# Sheet3.net
KiCad netlist of a schematic drawn in Altium Designer
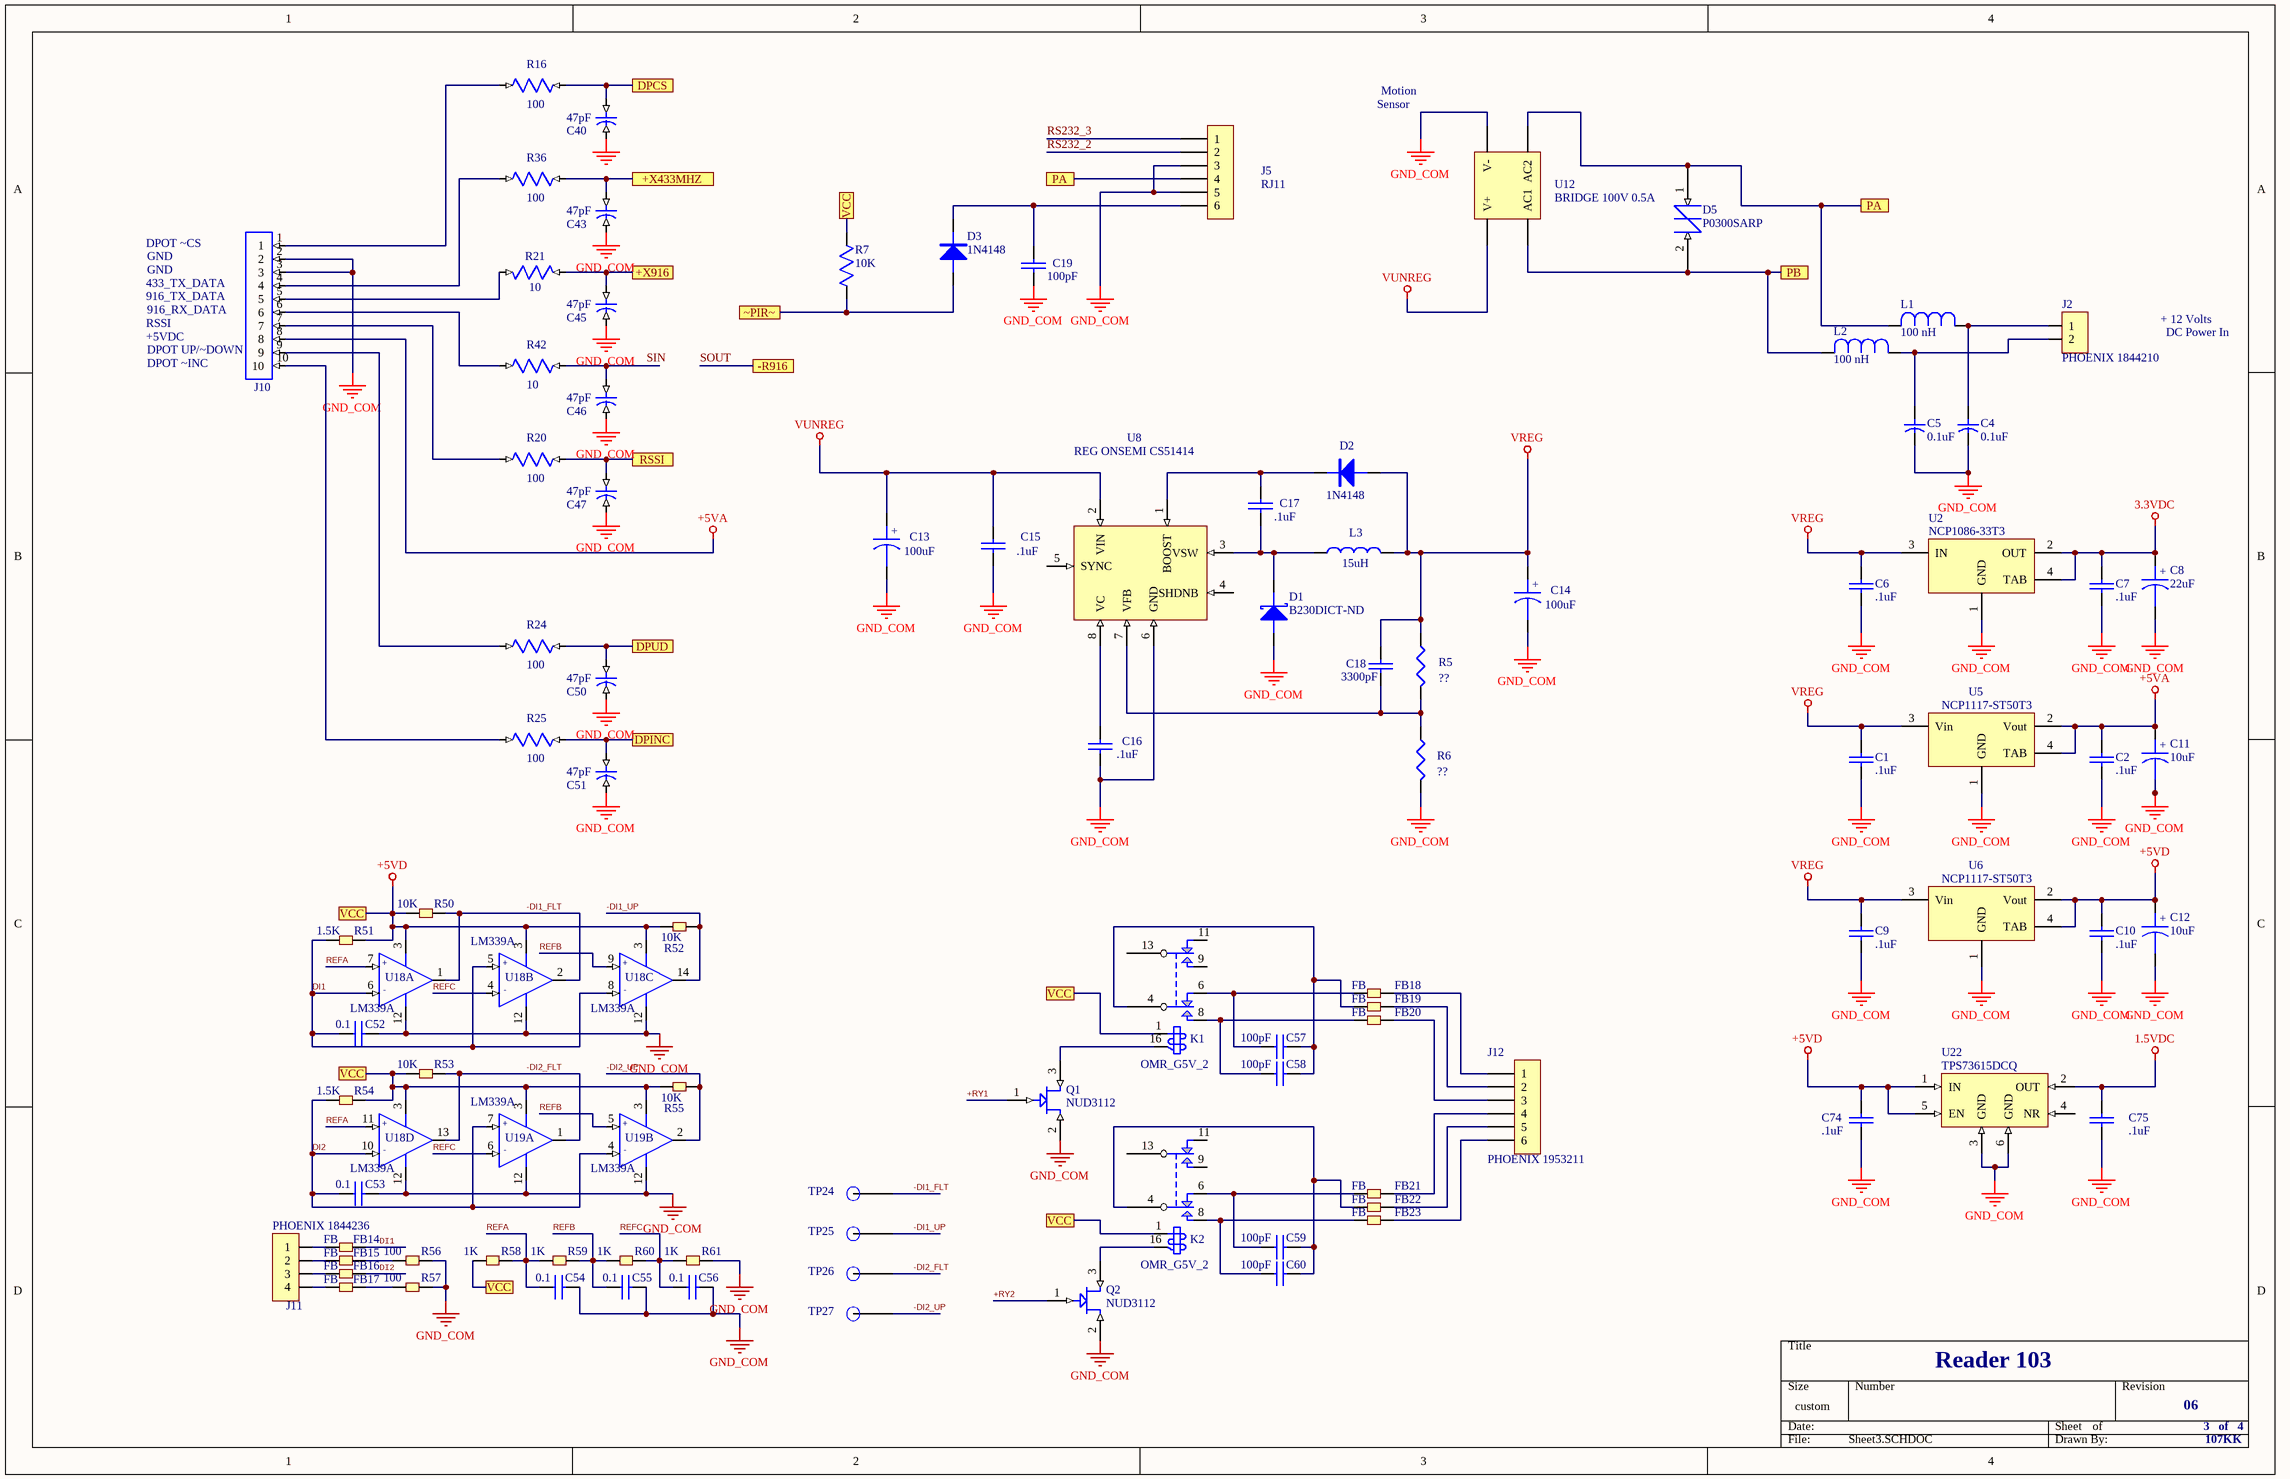
[diagram p0: Sheet3.SCHDOC]

(export (version "E")
  (design (tool "Eeschema 10.0.6"))
  (components
    (comp (ref "C1")
      (value ".1uF")
      (footprint "0603")
      (description "Capacitor")
      (libsource (lib "*") (part "CAP"))
    )
    (comp (ref "C2")
      (value ".1uF")
      (footprint "0603")
      (description "Capacitor")
      (libsource (lib "*") (part "CAP"))
    )
    (comp (ref "C4") (value "0.1uF") (footprint "0603") (libsource (lib "*") (part "C_0603")))
    (comp (ref "C5") (value "0.1uF") (footprint "0603") (libsource (lib "*") (part "C_0603")))
    (comp (ref "C6")
      (value ".1uF")
      (footprint "0603")
      (description "Capacitor")
      (libsource (lib "*") (part "CAP"))
    )
    (comp (ref "C7")
      (value ".1uF")
      (footprint "0603")
      (description "Capacitor")
      (libsource (lib "*") (part "CAP"))
    )
    (comp (ref "C8")
      (value "22uF")
      (footprint "CAP A CASE")
      (description "Capacitor")
      (libsource (lib "*") (part "CAPACITOR POL"))
    )
    (comp (ref "C9")
      (value ".1uF")
      (footprint "0603")
      (description "Capacitor")
      (libsource (lib "*") (part "CAP"))
    )
    (comp (ref "C10")
      (value ".1uF")
      (footprint "0603")
      (description "Capacitor")
      (libsource (lib "*") (part "CAP"))
    )
    (comp (ref "C11")
      (value "10uF")
      (footprint "CAP A CASE")
      (description "Capacitor")
      (libsource (lib "*") (part "CAPACITOR POL"))
    )
    (comp (ref "C12")
      (value "10uF")
      (footprint "CAP A CASE")
      (description "Capacitor")
      (libsource (lib "*") (part "CAPACITOR POL"))
    )
    (comp (ref "C13")
      (value "100uF")
      (footprint "CAP D CASE")
      (description "Capacitor")
      (libsource (lib "*") (part "CAPACITOR POL"))
    )
    (comp (ref "C14")
      (value "100uF")
      (footprint "CAP D CASE")
      (description "Capacitor")
      (libsource (lib "*") (part "CAPACITOR POL"))
    )
    (comp (ref "C15")
      (value ".1uF")
      (footprint "0603")
      (description "Capacitor")
      (libsource (lib "*") (part "CAP"))
    )
    (comp (ref "C16")
      (value ".1uF")
      (footprint "0603")
      (description "Capacitor")
      (libsource (lib "*") (part "CAP"))
    )
    (comp (ref "C17")
      (value ".1uF")
      (footprint "0603")
      (description "Capacitor")
      (libsource (lib "*") (part "CAP"))
    )
    (comp (ref "C18")
      (value "3300pF")
      (footprint "0603")
      (description "Capacitor")
      (libsource (lib "*") (part "CAP"))
    )
    (comp (ref "C19")
      (value "100pF")
      (footprint "0603")
      (description "Capacitor")
      (libsource (lib "*") (part "CAP"))
    )
    (comp (ref "C40") (value "47pF") (footprint "0603") (libsource (lib "*") (part "C0603")))
    (comp (ref "C43") (value "47pF") (footprint "0603") (libsource (lib "*") (part "C0603")))
    (comp (ref "C45") (value "47pF") (footprint "0603") (libsource (lib "*") (part "C0603")))
    (comp (ref "C46") (value "47pF") (footprint "0603") (libsource (lib "*") (part "C0603")))
    (comp (ref "C47") (value "47pF") (footprint "0603") (libsource (lib "*") (part "C0603")))
    (comp (ref "C50") (value "47pF") (footprint "0603") (libsource (lib "*") (part "C0603")))
    (comp (ref "C51") (value "47pF") (footprint "0603") (libsource (lib "*") (part "C0603")))
    (comp (ref "C52") (value "0.1") (footprint "0603") (libsource (lib "*") (part "CAP NP_1")))
    (comp (ref "C53") (value "0.1") (footprint "0603") (libsource (lib "*") (part "CAP NP_1")))
    (comp (ref "C54") (value "0.1") (footprint "0603") (libsource (lib "*") (part "CAP NP_1")))
    (comp (ref "C55") (value "0.1") (footprint "0603") (libsource (lib "*") (part "CAP NP_1")))
    (comp (ref "C56") (value "0.1") (footprint "0603") (libsource (lib "*") (part "CAP NP_1")))
    (comp (ref "C57") (value "100pF") (footprint "0603") (libsource (lib "*") (part "CAP NP_1")))
    (comp (ref "C58") (value "100pF") (footprint "0603") (libsource (lib "*") (part "CAP NP_1")))
    (comp (ref "C59") (value "100pF") (footprint "0603") (libsource (lib "*") (part "CAP NP_1")))
    (comp (ref "C60") (value "100pF") (footprint "0603") (libsource (lib "*") (part "CAP NP_1")))
    (comp (ref "C74")
      (value ".1uF")
      (footprint "0603")
      (description "Capacitor")
      (libsource (lib "*") (part "CAP"))
    )
    (comp (ref "C75")
      (value ".1uF")
      (footprint "0603")
      (description "Capacitor")
      (libsource (lib "*") (part "CAP"))
    )
    (comp (ref "D1")
      (value "B230DICT-ND")
      (footprint "DIODE SMB")
      (description "Schottky Diode")
      (libsource (lib "*") (part "DIODE SCHOTTKY"))
    )
    (comp (ref "D2")
      (value "1N4148")
      (footprint "SOD123")
      (description "Diode")
      (libsource (lib "*") (part "DIODE"))
    )
    (comp (ref "D3")
      (value "1N4148")
      (footprint "SOD123")
      (description "Diode")
      (libsource (lib "*") (part "DIODE"))
    )
    (comp (ref "D5") (value "P0300SARP") (footprint "TRANSORB_1") (libsource (lib "*") (part "TRANSORB")))
    (comp (ref "FB14") (value "FB") (footprint "0603") (libsource (lib "*") (part "FB")))
    (comp (ref "FB15") (value "FB") (footprint "0603") (libsource (lib "*") (part "FB")))
    (comp (ref "FB16") (value "FB") (footprint "0603") (libsource (lib "*") (part "FB")))
    (comp (ref "FB17") (value "FB") (footprint "0603") (libsource (lib "*") (part "FB")))
    (comp (ref "FB18") (value "FB") (footprint "0603") (libsource (lib "*") (part "FB")))
    (comp (ref "FB19") (value "FB") (footprint "0603") (libsource (lib "*") (part "FB")))
    (comp (ref "FB20") (value "FB") (footprint "0603") (libsource (lib "*") (part "FB")))
    (comp (ref "FB21") (value "FB") (footprint "0603") (libsource (lib "*") (part "FB")))
    (comp (ref "FB22") (value "FB") (footprint "0603") (libsource (lib "*") (part "FB")))
    (comp (ref "FB23") (value "FB") (footprint "0603") (libsource (lib "*") (part "FB")))
    (comp (ref "J2")
      (value "PHOENIX 1844210")
      (footprint "CONN PHOENIX 1844210-2")
      (description "Connector")
      (libsource (lib "*") (part "CON2"))
    )
    (comp (ref "J5")
      (value "RJ11")
      (footprint "RJ11")
      (description "Connector")
      (libsource (lib "*") (part "CON6"))
    )
    (comp (ref "J10") (value "1X10 HEADER") (footprint "HDR_10") (libsource (lib "*") (part "HDR10")))
    (comp (ref "J11")
      (value "PHOENIX 1844236")
      (footprint "CONN PHOENIX 1844236-4")
      (libsource (lib "*") (part "CON4"))
    )
    (comp (ref "J12")
      (value "PHOENIX 1953211")
      (footprint "CONN PHOENIX 1953211-6")
      (description "Connector")
      (libsource (lib "*") (part "CON6"))
    )
    (comp (ref "K1") (value "OMR_G5V_2") (footprint "RELAY44") (libsource (lib "*") (part "OMRON_G5V_3")))
    (comp (ref "K2") (value "OMR_G5V_2") (footprint "RELAY44") (libsource (lib "*") (part "OMRON_G5V_3")))
    (comp (ref "L1") (value "100 nH") (footprint "0603") (libsource (lib "*") (part "INDUCTOR_1")))
    (comp (ref "L2") (value "100 nH") (footprint "0603") (libsource (lib "*") (part "INDUCTOR_1")))
    (comp (ref "L3")
      (value "15uH")
      (footprint "COIL COILTRONICS UP2B-150")
      (libsource (lib "*") (part "INDUCTOR1"))
    )
    (comp (ref "Q1")
      (value "NUD3112")
      (footprint "SOT23")
      (libsource (lib "*") (part "INDUCTIVE LOAD DRIVER"))
    )
    (comp (ref "Q2")
      (value "NUD3112")
      (footprint "SOT23")
      (libsource (lib "*") (part "INDUCTIVE LOAD DRIVER"))
    )
    (comp (ref "R5") (value "??") (footprint "0603") (libsource (lib "*") (part "RES1")))
    (comp (ref "R6") (value "??") (footprint "0603") (libsource (lib "*") (part "RES1")))
    (comp (ref "R7") (value "10K") (footprint "0603") (libsource (lib "*") (part "R_0603")))
    (comp (ref "R16") (value "100") (footprint "0603") (libsource (lib "*") (part "R0603")))
    (comp (ref "R20") (value "100") (footprint "0603") (libsource (lib "*") (part "R0603")))
    (comp (ref "R21") (value "10") (footprint "0603") (libsource (lib "*") (part "R_603")))
    (comp (ref "R24") (value "100") (footprint "0603") (libsource (lib "*") (part "R0603")))
    (comp (ref "R25") (value "100") (footprint "0603") (libsource (lib "*") (part "R0603")))
    (comp (ref "R36") (value "100") (footprint "0603") (libsource (lib "*") (part "R0603")))
    (comp (ref "R42") (value "10") (footprint "0603") (libsource (lib "*") (part "R0603")))
    (comp (ref "R50") (value "10K") (footprint "0603") (libsource (lib "*") (part "RS")))
    (comp (ref "R51") (value "1.5K") (footprint "0603") (libsource (lib "*") (part "RS")))
    (comp (ref "R52") (value "10K") (footprint "0603") (libsource (lib "*") (part "RS")))
    (comp (ref "R53") (value "10K") (footprint "0603") (libsource (lib "*") (part "RS")))
    (comp (ref "R54") (value "1.5K") (footprint "0603") (libsource (lib "*") (part "RS")))
    (comp (ref "R55") (value "10K") (footprint "0603") (libsource (lib "*") (part "RS")))
    (comp (ref "R56") (value "100") (footprint "0603") (libsource (lib "*") (part "RS")))
    (comp (ref "R57") (value "100") (footprint "0603") (libsource (lib "*") (part "RS")))
    (comp (ref "R58") (value "1K") (footprint "0603") (libsource (lib "*") (part "RS")))
    (comp (ref "R59") (value "1K") (footprint "0603") (libsource (lib "*") (part "RS")))
    (comp (ref "R60") (value "1K") (footprint "0603") (libsource (lib "*") (part "RS")))
    (comp (ref "R61") (value "1K") (footprint "0603") (libsource (lib "*") (part "RS")))
    (comp (ref "TP24") (value "TP") (footprint "TEST POINT PAD 3") (libsource (lib "*") (part "TESTPOINT_1")))
    (comp (ref "TP25") (value "TP") (footprint "TEST POINT PAD 3") (libsource (lib "*") (part "TESTPOINT_1")))
    (comp (ref "TP26") (value "TP") (footprint "TEST POINT PAD 3") (libsource (lib "*") (part "TESTPOINT_1")))
    (comp (ref "TP27") (value "TP") (footprint "TEST POINT PAD 3") (libsource (lib "*") (part "TESTPOINT_1")))
    (comp (ref "U2")
      (value "NCP1086-33T3")
      (footprint "SOT223 REG")
      (libsource (lib "Reader-Rev6") (part "REG GOI"))
    )
    (comp (ref "U5")
      (value "NCP1117-ST50T3")
      (footprint "SOT223 REG")
      (libsource (lib "Reader-Rev6") (part "REG REVERSED"))
    )
    (comp (ref "U6")
      (value "NCP1117-ST50T3")
      (footprint "SOT223 REG")
      (libsource (lib "Reader-Rev6") (part "REG REVERSED"))
    )
    (comp (ref "U8")
      (value "REG ONSEMI CS51414")
      (footprint "SO8")
      (libsource (lib "*") (part "REG ONSEMI CS51414"))
    )
    (comp (ref "U12")
      (value "BRIDGE 100V 0.5A")
      (footprint "BRIDGE")
      (description "Diode Bridge")
      (libsource (lib "*") (part "BRIDGE2"))
    )
    (comp (ref "U18") (value "LM339A") (footprint "SO14") (libsource (lib "*") (part "LM339")))
    (comp (ref "U19") (value "LM339A") (footprint "SO14") (libsource (lib "*") (part "LM339")))
    (comp (ref "U22")
      (value "TPS73615DCQ")
      (footprint "SOT223-5")
      (libsource (lib "*") (part "REG SOT223-5"))
    )
  )
  (nets
    (net (code "1") (name "+5VA") (class "Default")
      (node (ref "C11") (pin "1") (pinfunction "1_1") (pintype "passive"))
      (node (ref "C2") (pin "1") (pinfunction "1_1") (pintype "passive"))
      (node (ref "J10") (pin "8") (pinfunction "8_8") (pintype "input"))
      (node (ref "U5") (pin "2") (pinfunction "Vout_2") (pintype "passive"))
      (node (ref "U5") (pin "4") (pinfunction "TAB_4") (pintype "passive"))
    )
    (net (code "2") (name "+5VD") (class "Default")
      (node (ref "C10") (pin "1") (pinfunction "1_1") (pintype "passive"))
      (node (ref "C12") (pin "1") (pinfunction "1_1") (pintype "passive"))
      (node (ref "C74") (pin "1") (pinfunction "1_1") (pintype "passive"))
      (node (ref "K1") (pin "1") (pinfunction "COIL1_1") (pintype "passive"))
      (node (ref "K2") (pin "1") (pinfunction "COIL1_1") (pintype "passive"))
      (node (ref "R50") (pin "2") (pinfunction "2_2") (pintype "passive"))
      (node (ref "R51") (pin "1") (pinfunction "1_1") (pintype "passive"))
      (node (ref "R52") (pin "2") (pinfunction "2_2") (pintype "passive"))
      (node (ref "R53") (pin "2") (pinfunction "2_2") (pintype "passive"))
      (node (ref "R54") (pin "1") (pinfunction "1_1") (pintype "passive"))
      (node (ref "R55") (pin "2") (pinfunction "2_2") (pintype "passive"))
      (node (ref "R58") (pin "2") (pinfunction "2_2") (pintype "passive"))
      (node (ref "R7") (pin "1") (pinfunction "A_1") (pintype "passive"))
      (node (ref "U18") (pin "3") (pinfunction "V+_3") (pintype "power_in"))
      (node (ref "U19") (pin "3") (pinfunction "V+_3") (pintype "power_in"))
      (node (ref "U22") (pin "1") (pinfunction "IN_1") (pintype "input"))
      (node (ref "U22") (pin "5") (pinfunction "EN_5") (pintype "input"))
      (node (ref "U6") (pin "2") (pinfunction "Vout_2") (pintype "passive"))
      (node (ref "U6") (pin "4") (pinfunction "TAB_4") (pintype "passive"))
    )
    (net (code "3") (name "/+RY1") (class "Default")
      (node (ref "Q1") (pin "1") (pinfunction "G_1") (pintype "input"))
    )
    (net (code "4") (name "/+RY2") (class "Default")
      (node (ref "Q2") (pin "1") (pinfunction "G_1") (pintype "input"))
    )
    (net (code "5") (name "/+X433MHZ") (class "Default")
      (node (ref "C43") (pin "1") (pinfunction "A_1") (pintype "input"))
      (node (ref "R36") (pin "2") (pinfunction "B_2") (pintype "input"))
    )
    (net (code "6") (name "/+X916") (class "Default")
      (node (ref "C45") (pin "1") (pinfunction "A_1") (pintype "input"))
      (node (ref "R21") (pin "1") (pinfunction "A_1") (pintype "input"))
    )
    (net (code "7") (name "/-DI1_FLT") (class "Default")
      (node (ref "R50") (pin "1") (pinfunction "1_1") (pintype "passive"))
      (node (ref "TP24") (pin "1") (pinfunction "TP_1") (pintype "passive"))
      (node (ref "U18") (pin "1") (pinfunction "OUT_1") (pintype "open_collector"))
      (node (ref "U18") (pin "2") (pinfunction "OUT_2") (pintype "open_collector"))
    )
    (net (code "8") (name "/-DI1_UP") (class "Default")
      (node (ref "R52") (pin "1") (pinfunction "1_1") (pintype "passive"))
      (node (ref "TP25") (pin "1") (pinfunction "TP_1") (pintype "passive"))
      (node (ref "U18") (pin "14") (pinfunction "OUT_14") (pintype "open_collector"))
    )
    (net (code "9") (name "/-DI2_FLT") (class "Default")
      (node (ref "R53") (pin "1") (pinfunction "1_1") (pintype "passive"))
      (node (ref "TP26") (pin "1") (pinfunction "TP_1") (pintype "passive"))
      (node (ref "U18") (pin "13") (pinfunction "OUT_13") (pintype "open_collector"))
      (node (ref "U19") (pin "1") (pinfunction "OUT_1") (pintype "open_collector"))
    )
    (net (code "10") (name "/-DI2_UP") (class "Default")
      (node (ref "R55") (pin "1") (pinfunction "1_1") (pintype "passive"))
      (node (ref "TP27") (pin "1") (pinfunction "TP_1") (pintype "passive"))
      (node (ref "U19") (pin "2") (pinfunction "OUT_2") (pintype "open_collector"))
    )
    (net (code "11") (name "/DI1") (class "Default")
      (node (ref "C52") (pin "1") (pinfunction "1_1") (pintype "passive"))
      (node (ref "FB14") (pin "1") (pinfunction "1_1") (pintype "passive"))
      (node (ref "R51") (pin "2") (pinfunction "2_2") (pintype "passive"))
      (node (ref "U18") (pin "5") (pinfunction "+_5") (pintype "input"))
      (node (ref "U18") (pin "6") (pinfunction "-_6") (pintype "input"))
      (node (ref "U18") (pin "8") (pinfunction "-_8") (pintype "input"))
    )
    (net (code "12") (name "/DI2") (class "Default")
      (node (ref "C53") (pin "1") (pinfunction "1_1") (pintype "passive"))
      (node (ref "FB16") (pin "1") (pinfunction "1_1") (pintype "passive"))
      (node (ref "R54") (pin "2") (pinfunction "2_2") (pintype "passive"))
      (node (ref "U18") (pin "10") (pinfunction "-_10") (pintype "input"))
      (node (ref "U19") (pin "4") (pinfunction "-_4") (pintype "input"))
      (node (ref "U19") (pin "7") (pinfunction "+_7") (pintype "input"))
    )
    (net (code "13") (name "/DPCS") (class "Default")
      (node (ref "C40") (pin "1") (pinfunction "A_1") (pintype "input"))
      (node (ref "R16") (pin "2") (pinfunction "B_2") (pintype "input"))
    )
    (net (code "14") (name "/DPINC") (class "Default")
      (node (ref "C51") (pin "1") (pinfunction "A_1") (pintype "input"))
      (node (ref "R25") (pin "2") (pinfunction "B_2") (pintype "input"))
    )
    (net (code "15") (name "/DPUD") (class "Default")
      (node (ref "C50") (pin "1") (pinfunction "A_1") (pintype "input"))
      (node (ref "R24") (pin "2") (pinfunction "B_2") (pintype "input"))
    )
    (net (code "16") (name "/PA") (class "Default")
      (node (ref "D5") (pin "1") (pinfunction "1_1") (pintype "input"))
      (node (ref "J5") (pin "4") (pinfunction "4_4") (pintype "passive"))
      (node (ref "L1") (pin "1") (pinfunction "B_1") (pintype "passive"))
      (node (ref "U12") (pin "AC2") (pinfunction "AC2_AC2") (pintype "passive"))
    )
    (net (code "17") (name "/PB") (class "Default")
      (node (ref "D5") (pin "2") (pinfunction "2_2") (pintype "input"))
      (node (ref "L2") (pin "1") (pinfunction "B_1") (pintype "passive"))
      (node (ref "U12") (pin "AC1") (pinfunction "AC1_AC1") (pintype "passive"))
    )
    (net (code "18") (name "/REFA") (class "Default")
      (node (ref "C54") (pin "1") (pinfunction "1_1") (pintype "passive"))
      (node (ref "R58") (pin "1") (pinfunction "1_1") (pintype "passive"))
      (node (ref "R59") (pin "2") (pinfunction "2_2") (pintype "passive"))
      (node (ref "U18") (pin "11") (pinfunction "+_11") (pintype "input"))
      (node (ref "U18") (pin "7") (pinfunction "+_7") (pintype "input"))
    )
    (net (code "19") (name "/REFB") (class "Default")
      (node (ref "C55") (pin "1") (pinfunction "1_1") (pintype "passive"))
      (node (ref "R59") (pin "1") (pinfunction "1_1") (pintype "passive"))
      (node (ref "R60") (pin "2") (pinfunction "2_2") (pintype "passive"))
      (node (ref "U18") (pin "9") (pinfunction "+_9") (pintype "input"))
      (node (ref "U19") (pin "5") (pinfunction "+_5") (pintype "input"))
    )
    (net (code "20") (name "/REFC") (class "Default")
      (node (ref "C56") (pin "1") (pinfunction "1_1") (pintype "passive"))
      (node (ref "R60") (pin "1") (pinfunction "1_1") (pintype "passive"))
      (node (ref "R61") (pin "2") (pinfunction "2_2") (pintype "passive"))
      (node (ref "U18") (pin "4") (pinfunction "-_4") (pintype "input"))
      (node (ref "U19") (pin "6") (pinfunction "-_6") (pintype "input"))
    )
    (net (code "21") (name "/RS232_2") (class "Default")
      (node (ref "J5") (pin "2") (pinfunction "2_2") (pintype "passive"))
    )
    (net (code "22") (name "/RS232_3") (class "Default")
      (node (ref "J5") (pin "1") (pinfunction "1_1") (pintype "passive"))
    )
    (net (code "23") (name "/RSSI") (class "Default")
      (node (ref "C47") (pin "1") (pinfunction "A_1") (pintype "input"))
      (node (ref "R20") (pin "2") (pinfunction "B_2") (pintype "input"))
    )
    (net (code "24") (name "/SIN") (class "Default")
      (node (ref "C46") (pin "1") (pinfunction "A_1") (pintype "input"))
      (node (ref "R42") (pin "2") (pinfunction "B_2") (pintype "input"))
    )
    (net (code "26") (name "/~PIR~") (class "Default")
      (node (ref "D3") (pin "A") (pinfunction "A_A") (pintype "passive"))
      (node (ref "R7") (pin "2") (pinfunction "B_2") (pintype "passive"))
    )
    (net (code "27") (name "1.5VDC") (class "Default")
      (node (ref "C75") (pin "1") (pinfunction "1_1") (pintype "passive"))
      (node (ref "U22") (pin "2") (pinfunction "OUT_2") (pintype "input"))
    )
    (net (code "28") (name "3.3VDC") (class "Default")
      (node (ref "C7") (pin "1") (pinfunction "1_1") (pintype "passive"))
      (node (ref "C8") (pin "1") (pinfunction "1_1") (pintype "passive"))
      (node (ref "U2") (pin "2") (pinfunction "OUT_2") (pintype "power_in"))
      (node (ref "U2") (pin "4") (pinfunction "TAB_4") (pintype "power_in"))
    )
    (net (code "29") (name "GND_COM") (class "Default")
      (node (ref "C1") (pin "2") (pinfunction "2_2") (pintype "passive"))
      (node (ref "C10") (pin "2") (pinfunction "2_2") (pintype "passive"))
      (node (ref "C11") (pin "2") (pinfunction "2_2") (pintype "passive"))
      (node (ref "C12") (pin "2") (pinfunction "2_2") (pintype "passive"))
      (node (ref "C13") (pin "2") (pinfunction "2_2") (pintype "passive"))
      (node (ref "C14") (pin "2") (pinfunction "2_2") (pintype "passive"))
      (node (ref "C15") (pin "2") (pinfunction "2_2") (pintype "passive"))
      (node (ref "C16") (pin "2") (pinfunction "2_2") (pintype "passive"))
      (node (ref "C19") (pin "2") (pinfunction "2_2") (pintype "passive"))
      (node (ref "C2") (pin "2") (pinfunction "2_2") (pintype "passive"))
      (node (ref "C4") (pin "2") (pinfunction "B_2") (pintype "passive"))
      (node (ref "C40") (pin "2") (pinfunction "B_2") (pintype "input"))
      (node (ref "C43") (pin "2") (pinfunction "B_2") (pintype "input"))
      (node (ref "C45") (pin "2") (pinfunction "B_2") (pintype "input"))
      (node (ref "C46") (pin "2") (pinfunction "B_2") (pintype "input"))
      (node (ref "C47") (pin "2") (pinfunction "B_2") (pintype "input"))
      (node (ref "C5") (pin "2") (pinfunction "B_2") (pintype "passive"))
      (node (ref "C50") (pin "2") (pinfunction "B_2") (pintype "input"))
      (node (ref "C51") (pin "2") (pinfunction "B_2") (pintype "input"))
      (node (ref "C52") (pin "2") (pinfunction "2_2") (pintype "passive"))
      (node (ref "C53") (pin "2") (pinfunction "2_2") (pintype "passive"))
      (node (ref "C54") (pin "2") (pinfunction "2_2") (pintype "passive"))
      (node (ref "C55") (pin "2") (pinfunction "2_2") (pintype "passive"))
      (node (ref "C56") (pin "2") (pinfunction "2_2") (pintype "passive"))
      (node (ref "C6") (pin "2") (pinfunction "2_2") (pintype "passive"))
      (node (ref "C7") (pin "2") (pinfunction "2_2") (pintype "passive"))
      (node (ref "C74") (pin "2") (pinfunction "2_2") (pintype "passive"))
      (node (ref "C75") (pin "2") (pinfunction "2_2") (pintype "passive"))
      (node (ref "C8") (pin "2") (pinfunction "2_2") (pintype "passive"))
      (node (ref "C9") (pin "2") (pinfunction "2_2") (pintype "passive"))
      (node (ref "D1") (pin "A") (pinfunction "A_A") (pintype "passive"))
      (node (ref "J10") (pin "2") (pinfunction "2_2") (pintype "input"))
      (node (ref "J10") (pin "3") (pinfunction "3_3") (pintype "input"))
      (node (ref "J5") (pin "3") (pinfunction "3_3") (pintype "passive"))
      (node (ref "J5") (pin "5") (pinfunction "5_5") (pintype "passive"))
      (node (ref "Q1") (pin "2") (pinfunction "S_2") (pintype "input"))
      (node (ref "Q2") (pin "2") (pinfunction "S_2") (pintype "input"))
      (node (ref "R56") (pin "1") (pinfunction "1_1") (pintype "passive"))
      (node (ref "R57") (pin "1") (pinfunction "1_1") (pintype "passive"))
      (node (ref "R6") (pin "2") (pinfunction "2_2") (pintype "passive"))
      (node (ref "R61") (pin "1") (pinfunction "1_1") (pintype "passive"))
      (node (ref "U12") (pin "V-") (pinfunction "V-_V-") (pintype "passive"))
      (node (ref "U18") (pin "12") (pinfunction "V-_12") (pintype "power_in"))
      (node (ref "U19") (pin "12") (pinfunction "V-_12") (pintype "power_in"))
      (node (ref "U2") (pin "1") (pinfunction "GND_1") (pintype "power_in"))
      (node (ref "U22") (pin "3") (pinfunction "GND_3") (pintype "input"))
      (node (ref "U22") (pin "6") (pinfunction "GND_6") (pintype "input"))
      (node (ref "U5") (pin "1") (pinfunction "GND_1") (pintype "passive"))
      (node (ref "U6") (pin "1") (pinfunction "GND_1") (pintype "passive"))
      (node (ref "U8") (pin "6") (pinfunction "GND_6") (pintype "input"))
    )
    (net (code "30") (name "Net-(C4-A)") (class "Default")
      (node (ref "C4") (pin "1") (pinfunction "A_1") (pintype "passive"))
      (node (ref "J2") (pin "1") (pinfunction "1_1") (pintype "passive"))
      (node (ref "L1") (pin "2") (pinfunction "A_2") (pintype "passive"))
    )
    (net (code "31") (name "Net-(C5-A)") (class "Default")
      (node (ref "C5") (pin "1") (pinfunction "A_1") (pintype "passive"))
      (node (ref "J2") (pin "2") (pinfunction "2_2") (pintype "passive"))
      (node (ref "L2") (pin "2") (pinfunction "A_2") (pintype "passive"))
    )
    (net (code "32") (name "Net-(C19-Pad1)") (class "Default")
      (node (ref "C19") (pin "1") (pinfunction "1_1") (pintype "passive"))
      (node (ref "D3") (pin "K") (pinfunction "K_K") (pintype "passive"))
      (node (ref "J5") (pin "6") (pinfunction "6_6") (pintype "passive"))
    )
    (net (code "33") (name "Net-(FB14-Pad2)") (class "Default")
      (node (ref "FB14") (pin "2") (pinfunction "2_2") (pintype "passive"))
      (node (ref "J11") (pin "1") (pinfunction "1_1") (pintype "passive"))
    )
    (net (code "34") (name "Net-(FB15-Pad1)") (class "Default")
      (node (ref "FB15") (pin "1") (pinfunction "1_1") (pintype "passive"))
      (node (ref "R56") (pin "2") (pinfunction "2_2") (pintype "passive"))
    )
    (net (code "35") (name "Net-(FB15-Pad2)") (class "Default")
      (node (ref "FB15") (pin "2") (pinfunction "2_2") (pintype "passive"))
      (node (ref "J11") (pin "2") (pinfunction "2_2") (pintype "passive"))
    )
    (net (code "36") (name "Net-(FB16-Pad2)") (class "Default")
      (node (ref "FB16") (pin "2") (pinfunction "2_2") (pintype "passive"))
      (node (ref "J11") (pin "3") (pinfunction "3_3") (pintype "passive"))
    )
    (net (code "37") (name "Net-(FB17-Pad1)") (class "Default")
      (node (ref "FB17") (pin "1") (pinfunction "1_1") (pintype "passive"))
      (node (ref "R57") (pin "2") (pinfunction "2_2") (pintype "passive"))
    )
    (net (code "38") (name "Net-(FB17-Pad2)") (class "Default")
      (node (ref "FB17") (pin "2") (pinfunction "2_2") (pintype "passive"))
      (node (ref "J11") (pin "4") (pinfunction "4_4") (pintype "passive"))
    )
    (net (code "39") (name "Net-(FB18-Pad1)") (class "Default")
      (node (ref "FB18") (pin "1") (pinfunction "1_1") (pintype "passive"))
      (node (ref "J12") (pin "1") (pinfunction "1_1") (pintype "passive"))
    )
    (net (code "40") (name "Net-(FB19-Pad1)") (class "Default")
      (node (ref "FB19") (pin "1") (pinfunction "1_1") (pintype "passive"))
      (node (ref "J12") (pin "2") (pinfunction "2_2") (pintype "passive"))
    )
    (net (code "41") (name "Net-(FB20-Pad1)") (class "Default")
      (node (ref "FB20") (pin "1") (pinfunction "1_1") (pintype "passive"))
      (node (ref "J12") (pin "3") (pinfunction "3_3") (pintype "passive"))
    )
    (net (code "42") (name "Net-(FB21-Pad1)") (class "Default")
      (node (ref "FB21") (pin "1") (pinfunction "1_1") (pintype "passive"))
      (node (ref "J12") (pin "4") (pinfunction "4_4") (pintype "passive"))
    )
    (net (code "43") (name "Net-(FB22-Pad1)") (class "Default")
      (node (ref "FB22") (pin "1") (pinfunction "1_1") (pintype "passive"))
      (node (ref "J12") (pin "5") (pinfunction "5_5") (pintype "passive"))
    )
    (net (code "44") (name "Net-(FB23-Pad1)") (class "Default")
      (node (ref "FB23") (pin "1") (pinfunction "1_1") (pintype "passive"))
      (node (ref "J12") (pin "6") (pinfunction "6_6") (pintype "passive"))
    )
    (net (code "45") (name "Net-(K1-COIL2)") (class "Default")
      (node (ref "K1") (pin "16") (pinfunction "COIL2_16") (pintype "passive"))
      (node (ref "Q1") (pin "3") (pinfunction "D_3") (pintype "input"))
    )
    (net (code "46") (name "Net-(K1-COMMON2)") (class "Default")
      (node (ref "C57") (pin "2") (pinfunction "2_2") (pintype "passive"))
      (node (ref "C58") (pin "2") (pinfunction "2_2") (pintype "passive"))
      (node (ref "FB19") (pin "2") (pinfunction "2_2") (pintype "passive"))
      (node (ref "K1") (pin "4") (pinfunction "COMMON2_4") (pintype "passive"))
    )
    (net (code "47") (name "Net-(K1-NC2)") (class "Default")
      (node (ref "C57") (pin "1") (pinfunction "1_1") (pintype "passive"))
      (node (ref "FB18") (pin "2") (pinfunction "2_2") (pintype "passive"))
      (node (ref "K1") (pin "6") (pinfunction "NC2_6") (pintype "passive"))
    )
    (net (code "48") (name "Net-(K1-NO2)") (class "Default")
      (node (ref "C58") (pin "1") (pinfunction "1_1") (pintype "passive"))
      (node (ref "FB20") (pin "2") (pinfunction "2_2") (pintype "passive"))
      (node (ref "K1") (pin "8") (pinfunction "NO2_8") (pintype "passive"))
    )
    (net (code "49") (name "Net-(K2-COIL2)") (class "Default")
      (node (ref "K2") (pin "16") (pinfunction "COIL2_16") (pintype "passive"))
      (node (ref "Q2") (pin "3") (pinfunction "D_3") (pintype "input"))
    )
    (net (code "50") (name "Net-(K2-COMMON2)") (class "Default")
      (node (ref "C59") (pin "2") (pinfunction "2_2") (pintype "passive"))
      (node (ref "C60") (pin "2") (pinfunction "2_2") (pintype "passive"))
      (node (ref "FB22") (pin "2") (pinfunction "2_2") (pintype "passive"))
      (node (ref "K2") (pin "4") (pinfunction "COMMON2_4") (pintype "passive"))
    )
    (net (code "51") (name "Net-(K2-NC2)") (class "Default")
      (node (ref "C59") (pin "1") (pinfunction "1_1") (pintype "passive"))
      (node (ref "FB21") (pin "2") (pinfunction "2_2") (pintype "passive"))
      (node (ref "K2") (pin "6") (pinfunction "NC2_6") (pintype "passive"))
    )
    (net (code "52") (name "Net-(K2-NO2)") (class "Default")
      (node (ref "C60") (pin "1") (pinfunction "1_1") (pintype "passive"))
      (node (ref "FB23") (pin "2") (pinfunction "2_2") (pintype "passive"))
      (node (ref "K2") (pin "8") (pinfunction "NO2_8") (pintype "passive"))
    )
    (net (code "53") (name "Net-(R16-A)") (class "Default")
      (node (ref "J10") (pin "1") (pinfunction "1_1") (pintype "input"))
      (node (ref "R16") (pin "1") (pinfunction "A_1") (pintype "input"))
    )
    (net (code "54") (name "Net-(R20-A)") (class "Default")
      (node (ref "J10") (pin "7") (pinfunction "7_7") (pintype "input"))
      (node (ref "R20") (pin "1") (pinfunction "A_1") (pintype "input"))
    )
    (net (code "55") (name "Net-(R21-B)") (class "Default")
      (node (ref "J10") (pin "5") (pinfunction "5_5") (pintype "input"))
      (node (ref "R21") (pin "2") (pinfunction "B_2") (pintype "input"))
    )
    (net (code "56") (name "Net-(R24-A)") (class "Default")
      (node (ref "J10") (pin "9") (pinfunction "9_9") (pintype "input"))
      (node (ref "R24") (pin "1") (pinfunction "A_1") (pintype "input"))
    )
    (net (code "57") (name "Net-(R25-A)") (class "Default")
      (node (ref "J10") (pin "10") (pinfunction "10_10") (pintype "input"))
      (node (ref "R25") (pin "1") (pinfunction "A_1") (pintype "input"))
    )
    (net (code "58") (name "Net-(R36-A)") (class "Default")
      (node (ref "J10") (pin "4") (pinfunction "4_4") (pintype "input"))
      (node (ref "R36") (pin "1") (pinfunction "A_1") (pintype "input"))
    )
    (net (code "59") (name "Net-(R42-A)") (class "Default")
      (node (ref "J10") (pin "6") (pinfunction "6_6") (pintype "input"))
      (node (ref "R42") (pin "1") (pinfunction "A_1") (pintype "input"))
    )
    (net (code "60") (name "Net-(U8-BOOST)") (class "Default")
      (node (ref "C17") (pin "1") (pinfunction "1_1") (pintype "passive"))
      (node (ref "D2") (pin "K") (pinfunction "K_K") (pintype "passive"))
      (node (ref "U8") (pin "1") (pinfunction "BOOST_1") (pintype "input"))
    )
    (net (code "61") (name "Net-(U8-VC)") (class "Default")
      (node (ref "C16") (pin "1") (pinfunction "1_1") (pintype "passive"))
      (node (ref "U8") (pin "8") (pinfunction "VC_8") (pintype "input"))
    )
    (net (code "62") (name "Net-(U8-VFB)") (class "Default")
      (node (ref "C18") (pin "2") (pinfunction "2_2") (pintype "passive"))
      (node (ref "R5") (pin "2") (pinfunction "2_2") (pintype "passive"))
      (node (ref "R6") (pin "1") (pinfunction "1_1") (pintype "passive"))
      (node (ref "U8") (pin "7") (pinfunction "VFB_7") (pintype "input"))
    )
    (net (code "63") (name "Net-(U8-VSW)") (class "Default")
      (node (ref "C17") (pin "2") (pinfunction "2_2") (pintype "passive"))
      (node (ref "D1") (pin "K") (pinfunction "K_K") (pintype "passive"))
      (node (ref "L3") (pin "1") (pinfunction "1_1") (pintype "passive"))
      (node (ref "U8") (pin "3") (pinfunction "VSW_3") (pintype "input"))
    )
    (net (code "64") (name "VREG") (class "Default")
      (node (ref "C1") (pin "1") (pinfunction "1_1") (pintype "passive"))
      (node (ref "C14") (pin "1") (pinfunction "1_1") (pintype "passive"))
      (node (ref "C18") (pin "1") (pinfunction "1_1") (pintype "passive"))
      (node (ref "C6") (pin "1") (pinfunction "1_1") (pintype "passive"))
      (node (ref "C9") (pin "1") (pinfunction "1_1") (pintype "passive"))
      (node (ref "D2") (pin "A") (pinfunction "A_A") (pintype "passive"))
      (node (ref "L3") (pin "2") (pinfunction "2_2") (pintype "passive"))
      (node (ref "R5") (pin "1") (pinfunction "1_1") (pintype "passive"))
      (node (ref "U2") (pin "3") (pinfunction "IN_3") (pintype "power_in"))
      (node (ref "U5") (pin "3") (pinfunction "Vin_3") (pintype "passive"))
      (node (ref "U6") (pin "3") (pinfunction "Vin_3") (pintype "passive"))
    )
    (net (code "65") (name "VUNREG") (class "Default")
      (node (ref "C13") (pin "1") (pinfunction "1_1") (pintype "passive"))
      (node (ref "C15") (pin "1") (pinfunction "1_1") (pintype "passive"))
      (node (ref "U12") (pin "V+") (pinfunction "V+_V+") (pintype "passive"))
      (node (ref "U8") (pin "2") (pinfunction "VIN_2") (pintype "input"))
    )
    (net (code "66") (name "unconnected-(K1-COMMON1-Pad13)") (class "Default")
      (node (ref "K1") (pin "13") (pinfunction "COMMON1_13") (pintype "passive"))
    )
    (net (code "67") (name "unconnected-(K1-NC1-Pad11)") (class "Default")
      (node (ref "K1") (pin "11") (pinfunction "NC1_11") (pintype "passive"))
    )
    (net (code "68") (name "unconnected-(K1-NO1-Pad9)") (class "Default")
      (node (ref "K1") (pin "9") (pinfunction "NO1_9") (pintype "passive"))
    )
    (net (code "69") (name "unconnected-(K2-COMMON1-Pad13)") (class "Default")
      (node (ref "K2") (pin "13") (pinfunction "COMMON1_13") (pintype "passive"))
    )
    (net (code "70") (name "unconnected-(K2-NC1-Pad11)") (class "Default")
      (node (ref "K2") (pin "11") (pinfunction "NC1_11") (pintype "passive"))
    )
    (net (code "71") (name "unconnected-(K2-NO1-Pad9)") (class "Default")
      (node (ref "K2") (pin "9") (pinfunction "NO1_9") (pintype "passive"))
    )
    (net (code "72") (name "unconnected-(U8-SHDNB-Pad4)") (class "Default")
      (node (ref "U8") (pin "4") (pinfunction "SHDNB_4") (pintype "input"))
    )
    (net (code "73") (name "unconnected-(U8-SYNC-Pad5)") (class "Default")
      (node (ref "U8") (pin "5") (pinfunction "SYNC_5") (pintype "input"))
    )
    (net (code "74") (name "unconnected-(U22-NR-Pad4)") (class "Default")
      (node (ref "U22") (pin "4") (pinfunction "NR_4") (pintype "input"))
    )
  )
)
